# i2c-8ch-mux.net
KiCad netlist of a schematic drawn in EAGLE
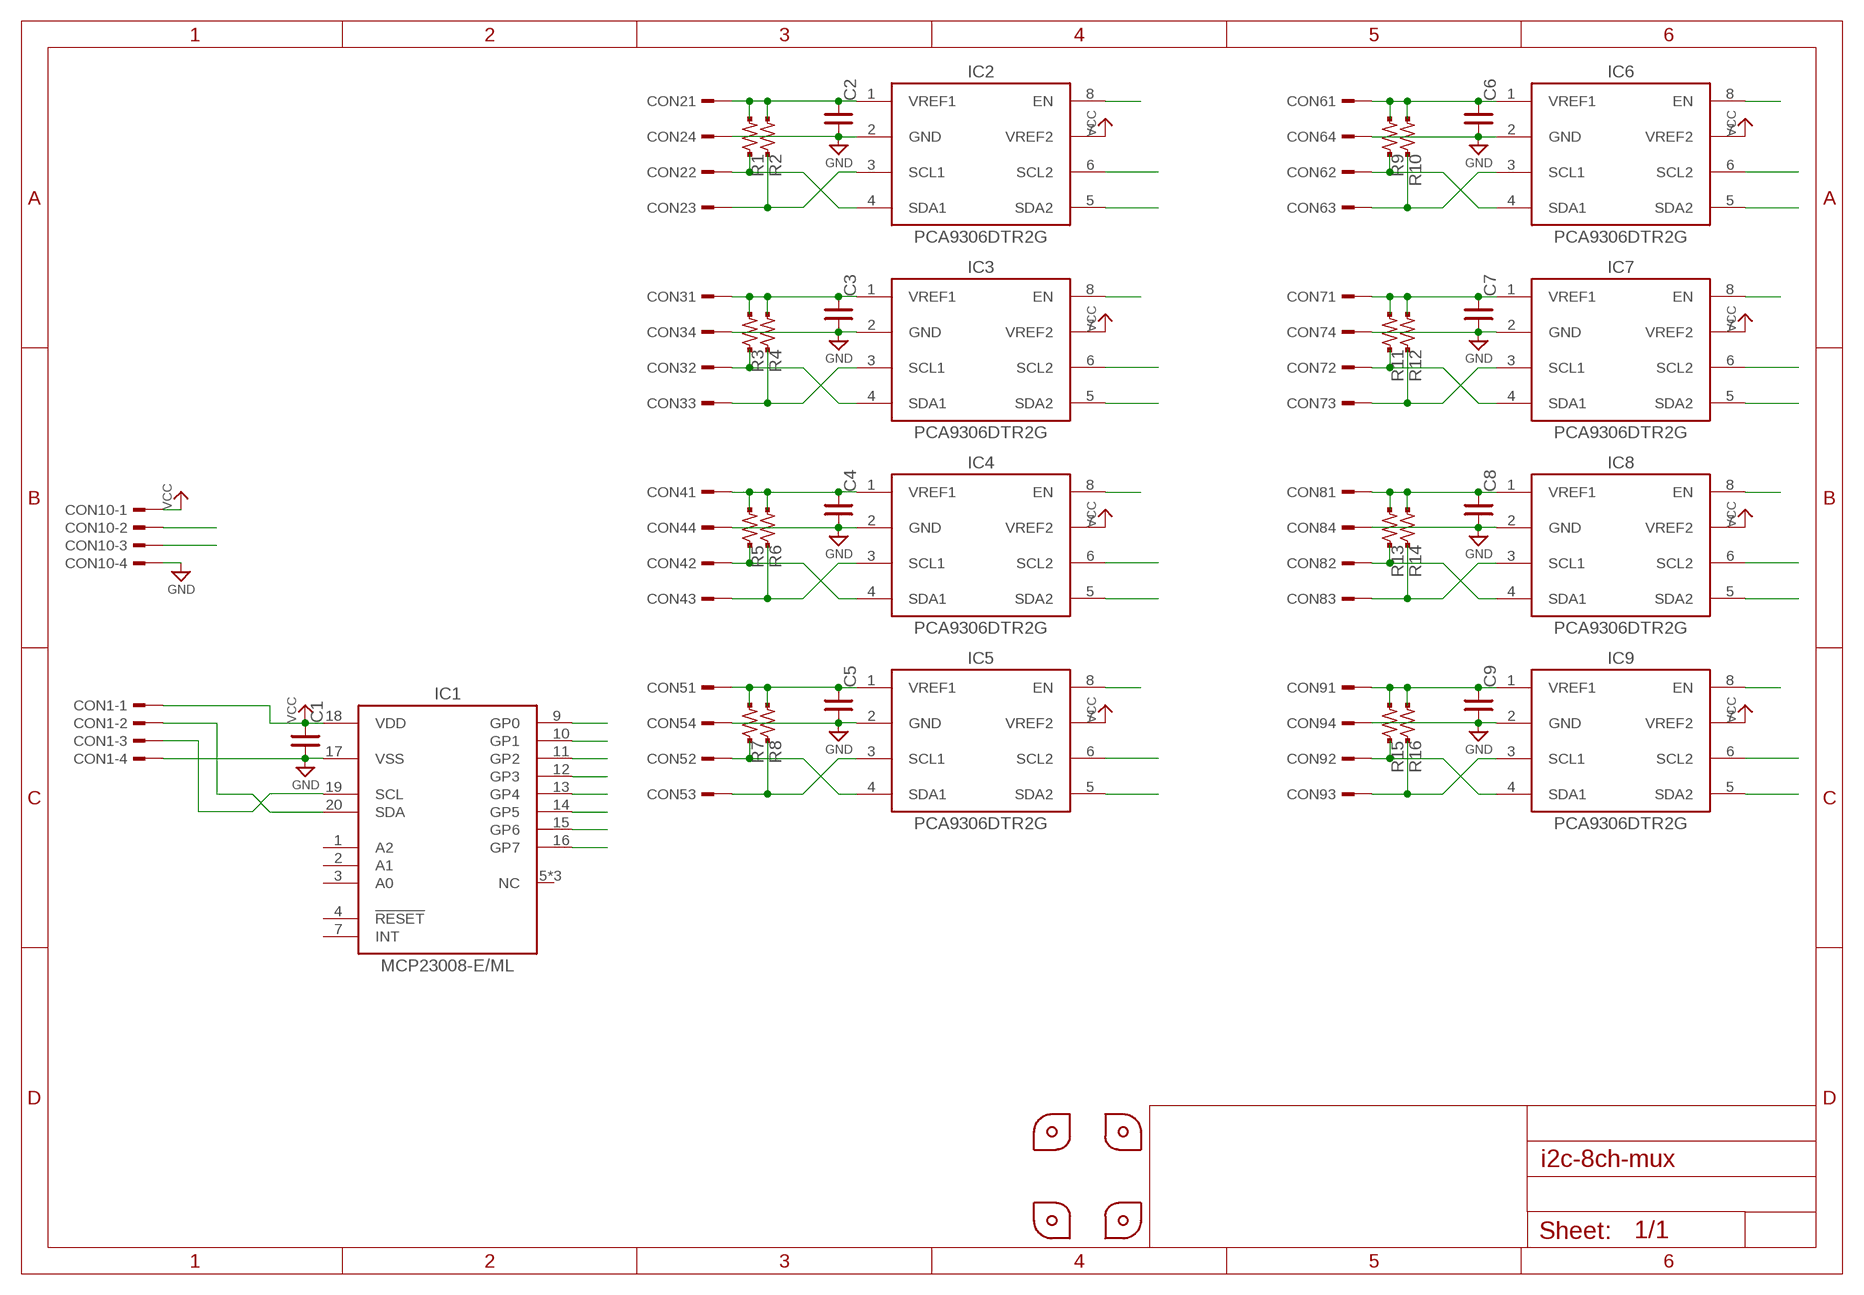
[diagram p0: schematic, sheet 1]

(export (version "E")
  (design (tool "Eeschema 10.0.6"))
  (components
    (comp (ref "C1")
      (value "C-SMD-0.1U-1005")
      (footprint "eagle-import:C0402")
      (libsource (lib "eagle-import") (part "C-SMD--10050.1U"))
    )
    (comp (ref "C2")
      (value "C-SMD-0.1U-1005")
      (footprint "eagle-import:C0402")
      (libsource (lib "eagle-import") (part "C-SMD--10050.1U"))
    )
    (comp (ref "C3")
      (value "C-SMD-0.1U-1005")
      (footprint "eagle-import:C0402")
      (libsource (lib "eagle-import") (part "C-SMD--10050.1U"))
    )
    (comp (ref "C4")
      (value "C-SMD-0.1U-1005")
      (footprint "eagle-import:C0402")
      (libsource (lib "eagle-import") (part "C-SMD--10050.1U"))
    )
    (comp (ref "C5")
      (value "C-SMD-0.1U-1005")
      (footprint "eagle-import:C0402")
      (libsource (lib "eagle-import") (part "C-SMD--10050.1U"))
    )
    (comp (ref "C6")
      (value "C-SMD-0.1U-1005")
      (footprint "eagle-import:C0402")
      (libsource (lib "eagle-import") (part "C-SMD--10050.1U"))
    )
    (comp (ref "C7")
      (value "C-SMD-0.1U-1005")
      (footprint "eagle-import:C0402")
      (libsource (lib "eagle-import") (part "C-SMD--10050.1U"))
    )
    (comp (ref "C8")
      (value "C-SMD-0.1U-1005")
      (footprint "eagle-import:C0402")
      (libsource (lib "eagle-import") (part "C-SMD--10050.1U"))
    )
    (comp (ref "C9")
      (value "C-SMD-0.1U-1005")
      (footprint "eagle-import:C0402")
      (libsource (lib "eagle-import") (part "C-SMD--10050.1U"))
    )
    (comp (ref "CON1")
      (value "S4B-XH-A")
      (footprint "eagle-import:S4B-XH-A(LF)(SN)")
      (libsource (lib "eagle-import") (part "S4B-XH-A"))
    )
    (comp (ref "CON2")
      (value "B4B-XH-A")
      (footprint "eagle-import:B4B-XH-A(LF)(SN)")
      (libsource (lib "eagle-import") (part "B4B-XH-A"))
    )
    (comp (ref "CON3")
      (value "B4B-XH-A")
      (footprint "eagle-import:B4B-XH-A(LF)(SN)")
      (libsource (lib "eagle-import") (part "B4B-XH-A"))
    )
    (comp (ref "CON4")
      (value "B4B-XH-A")
      (footprint "eagle-import:B4B-XH-A(LF)(SN)")
      (libsource (lib "eagle-import") (part "B4B-XH-A"))
    )
    (comp (ref "CON5")
      (value "B4B-XH-A")
      (footprint "eagle-import:B4B-XH-A(LF)(SN)")
      (libsource (lib "eagle-import") (part "B4B-XH-A"))
    )
    (comp (ref "CON6")
      (value "B4B-XH-A")
      (footprint "eagle-import:B4B-XH-A(LF)(SN)")
      (libsource (lib "eagle-import") (part "B4B-XH-A"))
    )
    (comp (ref "CON7")
      (value "B4B-XH-A")
      (footprint "eagle-import:B4B-XH-A(LF)(SN)")
      (libsource (lib "eagle-import") (part "B4B-XH-A"))
    )
    (comp (ref "CON8")
      (value "B4B-XH-A")
      (footprint "eagle-import:B4B-XH-A(LF)(SN)")
      (libsource (lib "eagle-import") (part "B4B-XH-A"))
    )
    (comp (ref "CON9")
      (value "B4B-XH-A")
      (footprint "eagle-import:B4B-XH-A(LF)(SN)")
      (libsource (lib "eagle-import") (part "B4B-XH-A"))
    )
    (comp (ref "CON10")
      (value "S4B-XH-A")
      (footprint "eagle-import:S4B-XH-A(LF)(SN)")
      (libsource (lib "eagle-import") (part "S4B-XH-A"))
    )
    (comp (ref "IC1")
      (value "MCP23008-E/ML")
      (footprint "eagle-import:QFN20-0.5P4.0X4.0")
      (libsource (lib "eagle-import") (part "MCP23008/ML-E"))
    )
    (comp (ref "IC2")
      (value "PCA9306DTR2G")
      (footprint "eagle-import:SOT65P440X300-8N")
      (libsource (lib "eagle-import") (part "PCA9306R2GDT"))
    )
    (comp (ref "IC3")
      (value "PCA9306DTR2G")
      (footprint "eagle-import:SOT65P440X300-8N")
      (libsource (lib "eagle-import") (part "PCA9306R2GDT"))
    )
    (comp (ref "IC4")
      (value "PCA9306DTR2G")
      (footprint "eagle-import:SOT65P440X300-8N")
      (libsource (lib "eagle-import") (part "PCA9306R2GDT"))
    )
    (comp (ref "IC5")
      (value "PCA9306DTR2G")
      (footprint "eagle-import:SOT65P440X300-8N")
      (libsource (lib "eagle-import") (part "PCA9306R2GDT"))
    )
    (comp (ref "IC6")
      (value "PCA9306DTR2G")
      (footprint "eagle-import:SOT65P440X300-8N")
      (libsource (lib "eagle-import") (part "PCA9306R2GDT"))
    )
    (comp (ref "IC7")
      (value "PCA9306DTR2G")
      (footprint "eagle-import:SOT65P440X300-8N")
      (libsource (lib "eagle-import") (part "PCA9306R2GDT"))
    )
    (comp (ref "IC8")
      (value "PCA9306DTR2G")
      (footprint "eagle-import:SOT65P440X300-8N")
      (libsource (lib "eagle-import") (part "PCA9306R2GDT"))
    )
    (comp (ref "IC9")
      (value "PCA9306DTR2G")
      (footprint "eagle-import:SOT65P440X300-8N")
      (libsource (lib "eagle-import") (part "PCA9306R2GDT"))
    )
    (comp (ref "P1")
      (value "PCB-CORNER")
      (footprint "eagle-import:PCB-CORNER")
      (libsource (lib "eagle-import") (part "PCB-CORNER"))
    )
    (comp (ref "P2")
      (value "PCB-CORNER")
      (footprint "eagle-import:PCB-CORNER")
      (libsource (lib "eagle-import") (part "PCB-CORNER"))
    )
    (comp (ref "P3")
      (value "PCB-CORNER")
      (footprint "eagle-import:PCB-CORNER")
      (libsource (lib "eagle-import") (part "PCB-CORNER"))
    )
    (comp (ref "P4")
      (value "PCB-CORNER")
      (footprint "eagle-import:PCB-CORNER")
      (libsource (lib "eagle-import") (part "PCB-CORNER"))
    )
    (comp (ref "R1")
      (value "R-US-10K-1005")
      (footprint "eagle-import:C0402")
      (libsource (lib "eagle-import") (part "R-US--100510K"))
    )
    (comp (ref "R2")
      (value "R-US-10K-1005")
      (footprint "eagle-import:C0402")
      (libsource (lib "eagle-import") (part "R-US--100510K"))
    )
    (comp (ref "R3")
      (value "R-US-10K-1005")
      (footprint "eagle-import:C0402")
      (libsource (lib "eagle-import") (part "R-US--100510K"))
    )
    (comp (ref "R4")
      (value "R-US-10K-1005")
      (footprint "eagle-import:C0402")
      (libsource (lib "eagle-import") (part "R-US--100510K"))
    )
    (comp (ref "R5")
      (value "R-US-10K-1005")
      (footprint "eagle-import:C0402")
      (libsource (lib "eagle-import") (part "R-US--100510K"))
    )
    (comp (ref "R6")
      (value "R-US-10K-1005")
      (footprint "eagle-import:C0402")
      (libsource (lib "eagle-import") (part "R-US--100510K"))
    )
    (comp (ref "R7")
      (value "R-US-10K-1005")
      (footprint "eagle-import:C0402")
      (libsource (lib "eagle-import") (part "R-US--100510K"))
    )
    (comp (ref "R8")
      (value "R-US-10K-1005")
      (footprint "eagle-import:C0402")
      (libsource (lib "eagle-import") (part "R-US--100510K"))
    )
    (comp (ref "R9")
      (value "R-US-10K-1005")
      (footprint "eagle-import:C0402")
      (libsource (lib "eagle-import") (part "R-US--100510K"))
    )
    (comp (ref "R10")
      (value "R-US-10K-1005")
      (footprint "eagle-import:C0402")
      (libsource (lib "eagle-import") (part "R-US--100510K"))
    )
    (comp (ref "R11")
      (value "R-US-10K-1005")
      (footprint "eagle-import:C0402")
      (libsource (lib "eagle-import") (part "R-US--100510K"))
    )
    (comp (ref "R12")
      (value "R-US-10K-1005")
      (footprint "eagle-import:C0402")
      (libsource (lib "eagle-import") (part "R-US--100510K"))
    )
    (comp (ref "R13")
      (value "R-US-10K-1005")
      (footprint "eagle-import:C0402")
      (libsource (lib "eagle-import") (part "R-US--100510K"))
    )
    (comp (ref "R14")
      (value "R-US-10K-1005")
      (footprint "eagle-import:C0402")
      (libsource (lib "eagle-import") (part "R-US--100510K"))
    )
    (comp (ref "R15")
      (value "R-US-10K-1005")
      (footprint "eagle-import:C0402")
      (libsource (lib "eagle-import") (part "R-US--100510K"))
    )
    (comp (ref "R16")
      (value "R-US-10K-1005")
      (footprint "eagle-import:C0402")
      (libsource (lib "eagle-import") (part "R-US--100510K"))
    )
  )
  (nets
    (net (code "1") (name "/N$6") (class "Default")
      (node (ref "IC1") (pin "10") (pinfunction "GP1_10") (pintype "bidirectional"))
      (node (ref "IC3") (pin "8") (pinfunction "EN_8") (pintype "bidirectional"))
    )
    (net (code "2") (name "/N$7") (class "Default")
      (node (ref "IC1") (pin "9") (pinfunction "GP0_9") (pintype "bidirectional"))
      (node (ref "IC2") (pin "8") (pinfunction "EN_8") (pintype "bidirectional"))
    )
    (net (code "3") (name "/N$8") (class "Default")
      (node (ref "IC1") (pin "11") (pinfunction "GP2_11") (pintype "bidirectional"))
      (node (ref "IC4") (pin "8") (pinfunction "EN_8") (pintype "bidirectional"))
    )
    (net (code "4") (name "/N$9") (class "Default")
      (node (ref "CON1") (pin "3") (pinfunction "1_3") (pintype "passive"))
      (node (ref "CON10") (pin "3") (pinfunction "1_3") (pintype "passive"))
      (node (ref "IC1") (pin "19") (pinfunction "SCL_19") (pintype "bidirectional"))
      (node (ref "IC2") (pin "6") (pinfunction "SCL2_6") (pintype "bidirectional"))
      (node (ref "IC3") (pin "6") (pinfunction "SCL2_6") (pintype "bidirectional"))
      (node (ref "IC4") (pin "6") (pinfunction "SCL2_6") (pintype "bidirectional"))
      (node (ref "IC5") (pin "6") (pinfunction "SCL2_6") (pintype "bidirectional"))
      (node (ref "IC6") (pin "6") (pinfunction "SCL2_6") (pintype "bidirectional"))
      (node (ref "IC7") (pin "6") (pinfunction "SCL2_6") (pintype "bidirectional"))
      (node (ref "IC8") (pin "6") (pinfunction "SCL2_6") (pintype "bidirectional"))
      (node (ref "IC9") (pin "6") (pinfunction "SCL2_6") (pintype "bidirectional"))
    )
    (net (code "5") (name "/N$10") (class "Default")
      (node (ref "CON1") (pin "2") (pinfunction "1_2") (pintype "passive"))
      (node (ref "CON10") (pin "2") (pinfunction "1_2") (pintype "passive"))
      (node (ref "IC1") (pin "20") (pinfunction "SDA_20") (pintype "bidirectional"))
      (node (ref "IC2") (pin "5") (pinfunction "SDA2_5") (pintype "bidirectional"))
      (node (ref "IC3") (pin "5") (pinfunction "SDA2_5") (pintype "bidirectional"))
      (node (ref "IC4") (pin "5") (pinfunction "SDA2_5") (pintype "bidirectional"))
      (node (ref "IC5") (pin "5") (pinfunction "SDA2_5") (pintype "bidirectional"))
      (node (ref "IC6") (pin "5") (pinfunction "SDA2_5") (pintype "bidirectional"))
      (node (ref "IC7") (pin "5") (pinfunction "SDA2_5") (pintype "bidirectional"))
      (node (ref "IC8") (pin "5") (pinfunction "SDA2_5") (pintype "bidirectional"))
      (node (ref "IC9") (pin "5") (pinfunction "SDA2_5") (pintype "bidirectional"))
    )
    (net (code "6") (name "/N$23") (class "Default")
      (node (ref "IC1") (pin "12") (pinfunction "GP3_12") (pintype "bidirectional"))
      (node (ref "IC5") (pin "8") (pinfunction "EN_8") (pintype "bidirectional"))
    )
    (net (code "7") (name "/N$24") (class "Default")
      (node (ref "IC1") (pin "13") (pinfunction "GP4_13") (pintype "bidirectional"))
      (node (ref "IC6") (pin "8") (pinfunction "EN_8") (pintype "bidirectional"))
    )
    (net (code "8") (name "/N$25") (class "Default")
      (node (ref "IC1") (pin "14") (pinfunction "GP5_14") (pintype "bidirectional"))
      (node (ref "IC7") (pin "8") (pinfunction "EN_8") (pintype "bidirectional"))
    )
    (net (code "9") (name "/N$26") (class "Default")
      (node (ref "IC1") (pin "15") (pinfunction "GP6_15") (pintype "bidirectional"))
      (node (ref "IC8") (pin "8") (pinfunction "EN_8") (pintype "bidirectional"))
    )
    (net (code "10") (name "/N$27") (class "Default")
      (node (ref "IC1") (pin "16") (pinfunction "GP7_16") (pintype "bidirectional"))
      (node (ref "IC9") (pin "8") (pinfunction "EN_8") (pintype "bidirectional"))
    )
    (net (code "11") (name "GND") (class "Default")
      (node (ref "C1") (pin "2") (pinfunction "2_2") (pintype "passive"))
      (node (ref "C2") (pin "2") (pinfunction "2_2") (pintype "passive"))
      (node (ref "C3") (pin "2") (pinfunction "2_2") (pintype "passive"))
      (node (ref "C4") (pin "2") (pinfunction "2_2") (pintype "passive"))
      (node (ref "C5") (pin "2") (pinfunction "2_2") (pintype "passive"))
      (node (ref "C6") (pin "2") (pinfunction "2_2") (pintype "passive"))
      (node (ref "C7") (pin "2") (pinfunction "2_2") (pintype "passive"))
      (node (ref "C8") (pin "2") (pinfunction "2_2") (pintype "passive"))
      (node (ref "C9") (pin "2") (pinfunction "2_2") (pintype "passive"))
      (node (ref "CON1") (pin "4") (pinfunction "1_4") (pintype "passive"))
      (node (ref "CON10") (pin "4") (pinfunction "1_4") (pintype "passive"))
      (node (ref "CON2") (pin "4") (pinfunction "1_4") (pintype "passive"))
      (node (ref "CON3") (pin "4") (pinfunction "1_4") (pintype "passive"))
      (node (ref "CON4") (pin "4") (pinfunction "1_4") (pintype "passive"))
      (node (ref "CON5") (pin "4") (pinfunction "1_4") (pintype "passive"))
      (node (ref "CON6") (pin "4") (pinfunction "1_4") (pintype "passive"))
      (node (ref "CON7") (pin "4") (pinfunction "1_4") (pintype "passive"))
      (node (ref "CON8") (pin "4") (pinfunction "1_4") (pintype "passive"))
      (node (ref "CON9") (pin "4") (pinfunction "1_4") (pintype "passive"))
      (node (ref "IC1") (pin "17") (pinfunction "VSS_17") (pintype "power_in"))
      (node (ref "IC2") (pin "2") (pinfunction "GND_2") (pintype "bidirectional"))
      (node (ref "IC3") (pin "2") (pinfunction "GND_2") (pintype "bidirectional"))
      (node (ref "IC4") (pin "2") (pinfunction "GND_2") (pintype "bidirectional"))
      (node (ref "IC5") (pin "2") (pinfunction "GND_2") (pintype "bidirectional"))
      (node (ref "IC6") (pin "2") (pinfunction "GND_2") (pintype "bidirectional"))
      (node (ref "IC7") (pin "2") (pinfunction "GND_2") (pintype "bidirectional"))
      (node (ref "IC8") (pin "2") (pinfunction "GND_2") (pintype "bidirectional"))
      (node (ref "IC9") (pin "2") (pinfunction "GND_2") (pintype "bidirectional"))
    )
    (net (code "12") (name "Net-(CON2B-1)") (class "Default")
      (node (ref "CON2") (pin "2") (pinfunction "1_2") (pintype "passive"))
      (node (ref "IC2") (pin "4") (pinfunction "SDA1_4") (pintype "bidirectional"))
      (node (ref "R1") (pin "1") (pinfunction "1_1") (pintype "passive"))
    )
    (net (code "13") (name "Net-(CON2C-1)") (class "Default")
      (node (ref "CON2") (pin "3") (pinfunction "1_3") (pintype "passive"))
      (node (ref "IC2") (pin "3") (pinfunction "SCL1_3") (pintype "bidirectional"))
      (node (ref "R2") (pin "1") (pinfunction "1_1") (pintype "passive"))
    )
    (net (code "14") (name "Net-(CON3B-1)") (class "Default")
      (node (ref "CON3") (pin "2") (pinfunction "1_2") (pintype "passive"))
      (node (ref "IC3") (pin "4") (pinfunction "SDA1_4") (pintype "bidirectional"))
      (node (ref "R3") (pin "1") (pinfunction "1_1") (pintype "passive"))
    )
    (net (code "15") (name "Net-(CON3C-1)") (class "Default")
      (node (ref "CON3") (pin "3") (pinfunction "1_3") (pintype "passive"))
      (node (ref "IC3") (pin "3") (pinfunction "SCL1_3") (pintype "bidirectional"))
      (node (ref "R4") (pin "1") (pinfunction "1_1") (pintype "passive"))
    )
    (net (code "16") (name "Net-(CON4B-1)") (class "Default")
      (node (ref "CON4") (pin "2") (pinfunction "1_2") (pintype "passive"))
      (node (ref "IC4") (pin "4") (pinfunction "SDA1_4") (pintype "bidirectional"))
      (node (ref "R5") (pin "1") (pinfunction "1_1") (pintype "passive"))
    )
    (net (code "17") (name "Net-(CON4C-1)") (class "Default")
      (node (ref "CON4") (pin "3") (pinfunction "1_3") (pintype "passive"))
      (node (ref "IC4") (pin "3") (pinfunction "SCL1_3") (pintype "bidirectional"))
      (node (ref "R6") (pin "1") (pinfunction "1_1") (pintype "passive"))
    )
    (net (code "18") (name "Net-(CON5B-1)") (class "Default")
      (node (ref "CON5") (pin "2") (pinfunction "1_2") (pintype "passive"))
      (node (ref "IC5") (pin "4") (pinfunction "SDA1_4") (pintype "bidirectional"))
      (node (ref "R7") (pin "1") (pinfunction "1_1") (pintype "passive"))
    )
    (net (code "19") (name "Net-(CON5C-1)") (class "Default")
      (node (ref "CON5") (pin "3") (pinfunction "1_3") (pintype "passive"))
      (node (ref "IC5") (pin "3") (pinfunction "SCL1_3") (pintype "bidirectional"))
      (node (ref "R8") (pin "1") (pinfunction "1_1") (pintype "passive"))
    )
    (net (code "20") (name "Net-(CON6B-1)") (class "Default")
      (node (ref "CON6") (pin "2") (pinfunction "1_2") (pintype "passive"))
      (node (ref "IC6") (pin "4") (pinfunction "SDA1_4") (pintype "bidirectional"))
      (node (ref "R9") (pin "1") (pinfunction "1_1") (pintype "passive"))
    )
    (net (code "21") (name "Net-(CON6C-1)") (class "Default")
      (node (ref "CON6") (pin "3") (pinfunction "1_3") (pintype "passive"))
      (node (ref "IC6") (pin "3") (pinfunction "SCL1_3") (pintype "bidirectional"))
      (node (ref "R10") (pin "1") (pinfunction "1_1") (pintype "passive"))
    )
    (net (code "22") (name "Net-(CON7B-1)") (class "Default")
      (node (ref "CON7") (pin "2") (pinfunction "1_2") (pintype "passive"))
      (node (ref "IC7") (pin "4") (pinfunction "SDA1_4") (pintype "bidirectional"))
      (node (ref "R11") (pin "1") (pinfunction "1_1") (pintype "passive"))
    )
    (net (code "23") (name "Net-(CON7C-1)") (class "Default")
      (node (ref "CON7") (pin "3") (pinfunction "1_3") (pintype "passive"))
      (node (ref "IC7") (pin "3") (pinfunction "SCL1_3") (pintype "bidirectional"))
      (node (ref "R12") (pin "1") (pinfunction "1_1") (pintype "passive"))
    )
    (net (code "24") (name "Net-(CON8B-1)") (class "Default")
      (node (ref "CON8") (pin "2") (pinfunction "1_2") (pintype "passive"))
      (node (ref "IC8") (pin "4") (pinfunction "SDA1_4") (pintype "bidirectional"))
      (node (ref "R13") (pin "1") (pinfunction "1_1") (pintype "passive"))
    )
    (net (code "25") (name "Net-(CON8C-1)") (class "Default")
      (node (ref "CON8") (pin "3") (pinfunction "1_3") (pintype "passive"))
      (node (ref "IC8") (pin "3") (pinfunction "SCL1_3") (pintype "bidirectional"))
      (node (ref "R14") (pin "1") (pinfunction "1_1") (pintype "passive"))
    )
    (net (code "26") (name "Net-(CON9B-1)") (class "Default")
      (node (ref "CON9") (pin "2") (pinfunction "1_2") (pintype "passive"))
      (node (ref "IC9") (pin "4") (pinfunction "SDA1_4") (pintype "bidirectional"))
      (node (ref "R15") (pin "1") (pinfunction "1_1") (pintype "passive"))
    )
    (net (code "27") (name "Net-(CON9C-1)") (class "Default")
      (node (ref "CON9") (pin "3") (pinfunction "1_3") (pintype "passive"))
      (node (ref "IC9") (pin "3") (pinfunction "SCL1_3") (pintype "bidirectional"))
      (node (ref "R16") (pin "1") (pinfunction "1_1") (pintype "passive"))
    )
    (net (code "28") (name "Net-(IC2-VREF1)") (class "Default")
      (node (ref "C2") (pin "1") (pinfunction "1_1") (pintype "passive"))
      (node (ref "CON2") (pin "1") (pinfunction "1_1") (pintype "passive"))
      (node (ref "IC2") (pin "1") (pinfunction "VREF1_1") (pintype "bidirectional"))
      (node (ref "R1") (pin "2") (pinfunction "2_2") (pintype "passive"))
      (node (ref "R2") (pin "2") (pinfunction "2_2") (pintype "passive"))
    )
    (net (code "29") (name "Net-(IC3-VREF1)") (class "Default")
      (node (ref "C3") (pin "1") (pinfunction "1_1") (pintype "passive"))
      (node (ref "CON3") (pin "1") (pinfunction "1_1") (pintype "passive"))
      (node (ref "IC3") (pin "1") (pinfunction "VREF1_1") (pintype "bidirectional"))
      (node (ref "R3") (pin "2") (pinfunction "2_2") (pintype "passive"))
      (node (ref "R4") (pin "2") (pinfunction "2_2") (pintype "passive"))
    )
    (net (code "30") (name "Net-(IC4-VREF1)") (class "Default")
      (node (ref "C4") (pin "1") (pinfunction "1_1") (pintype "passive"))
      (node (ref "CON4") (pin "1") (pinfunction "1_1") (pintype "passive"))
      (node (ref "IC4") (pin "1") (pinfunction "VREF1_1") (pintype "bidirectional"))
      (node (ref "R5") (pin "2") (pinfunction "2_2") (pintype "passive"))
      (node (ref "R6") (pin "2") (pinfunction "2_2") (pintype "passive"))
    )
    (net (code "31") (name "Net-(IC5-VREF1)") (class "Default")
      (node (ref "C5") (pin "1") (pinfunction "1_1") (pintype "passive"))
      (node (ref "CON5") (pin "1") (pinfunction "1_1") (pintype "passive"))
      (node (ref "IC5") (pin "1") (pinfunction "VREF1_1") (pintype "bidirectional"))
      (node (ref "R7") (pin "2") (pinfunction "2_2") (pintype "passive"))
      (node (ref "R8") (pin "2") (pinfunction "2_2") (pintype "passive"))
    )
    (net (code "32") (name "Net-(IC6-VREF1)") (class "Default")
      (node (ref "C6") (pin "1") (pinfunction "1_1") (pintype "passive"))
      (node (ref "CON6") (pin "1") (pinfunction "1_1") (pintype "passive"))
      (node (ref "IC6") (pin "1") (pinfunction "VREF1_1") (pintype "bidirectional"))
      (node (ref "R10") (pin "2") (pinfunction "2_2") (pintype "passive"))
      (node (ref "R9") (pin "2") (pinfunction "2_2") (pintype "passive"))
    )
    (net (code "33") (name "Net-(IC7-VREF1)") (class "Default")
      (node (ref "C7") (pin "1") (pinfunction "1_1") (pintype "passive"))
      (node (ref "CON7") (pin "1") (pinfunction "1_1") (pintype "passive"))
      (node (ref "IC7") (pin "1") (pinfunction "VREF1_1") (pintype "bidirectional"))
      (node (ref "R11") (pin "2") (pinfunction "2_2") (pintype "passive"))
      (node (ref "R12") (pin "2") (pinfunction "2_2") (pintype "passive"))
    )
    (net (code "34") (name "Net-(IC8-VREF1)") (class "Default")
      (node (ref "C8") (pin "1") (pinfunction "1_1") (pintype "passive"))
      (node (ref "CON8") (pin "1") (pinfunction "1_1") (pintype "passive"))
      (node (ref "IC8") (pin "1") (pinfunction "VREF1_1") (pintype "bidirectional"))
      (node (ref "R13") (pin "2") (pinfunction "2_2") (pintype "passive"))
      (node (ref "R14") (pin "2") (pinfunction "2_2") (pintype "passive"))
    )
    (net (code "35") (name "Net-(IC9-VREF1)") (class "Default")
      (node (ref "C9") (pin "1") (pinfunction "1_1") (pintype "passive"))
      (node (ref "CON9") (pin "1") (pinfunction "1_1") (pintype "passive"))
      (node (ref "IC9") (pin "1") (pinfunction "VREF1_1") (pintype "bidirectional"))
      (node (ref "R15") (pin "2") (pinfunction "2_2") (pintype "passive"))
      (node (ref "R16") (pin "2") (pinfunction "2_2") (pintype "passive"))
    )
    (net (code "36") (name "VCC") (class "Default")
      (node (ref "C1") (pin "1") (pinfunction "1_1") (pintype "passive"))
      (node (ref "CON1") (pin "1") (pinfunction "1_1") (pintype "passive"))
      (node (ref "CON10") (pin "1") (pinfunction "1_1") (pintype "passive"))
      (node (ref "IC1") (pin "18") (pinfunction "VDD_18") (pintype "power_in"))
      (node (ref "IC2") (pin "7") (pinfunction "VREF2_7") (pintype "bidirectional"))
      (node (ref "IC3") (pin "7") (pinfunction "VREF2_7") (pintype "bidirectional"))
      (node (ref "IC4") (pin "7") (pinfunction "VREF2_7") (pintype "bidirectional"))
      (node (ref "IC5") (pin "7") (pinfunction "VREF2_7") (pintype "bidirectional"))
      (node (ref "IC6") (pin "7") (pinfunction "VREF2_7") (pintype "bidirectional"))
      (node (ref "IC7") (pin "7") (pinfunction "VREF2_7") (pintype "bidirectional"))
      (node (ref "IC8") (pin "7") (pinfunction "VREF2_7") (pintype "bidirectional"))
      (node (ref "IC9") (pin "7") (pinfunction "VREF2_7") (pintype "bidirectional"))
    )
    (net (code "37") (name "unconnected-(IC1-A0-Pad3)") (class "Default")
      (node (ref "IC1") (pin "3") (pinfunction "A0_3") (pintype "bidirectional"))
    )
    (net (code "38") (name "unconnected-(IC1-A1-Pad2)") (class "Default")
      (node (ref "IC1") (pin "2") (pinfunction "A1_2") (pintype "bidirectional"))
    )
    (net (code "39") (name "unconnected-(IC1-A2-Pad1)") (class "Default")
      (node (ref "IC1") (pin "1") (pinfunction "A2_1") (pintype "bidirectional"))
    )
    (net (code "40") (name "unconnected-(IC1-INT-Pad7)") (class "Default")
      (node (ref "IC1") (pin "7") (pinfunction "INT_7") (pintype "bidirectional"))
    )
    (net (code "41") (name "unconnected-(IC1-NC-Pad5)") (class "Default")
      (node (ref "IC1") (pin "5") (pinfunction "NC_5") (pintype "no_connect"))
    )
    (net (code "42") (name "unconnected-(IC1-NC-Pad6)") (class "Default")
      (node (ref "IC1") (pin "6") (pinfunction "NC_6") (pintype "no_connect"))
    )
    (net (code "43") (name "unconnected-(IC1-NC-Pad8)") (class "Default")
      (node (ref "IC1") (pin "8") (pinfunction "NC_8") (pintype "no_connect"))
    )
    (net (code "44") (name "unconnected-(IC1-~{RESET}-Pad4)") (class "Default")
      (node (ref "IC1") (pin "4") (pinfunction "~{RESET}_4") (pintype "bidirectional"))
    )
  )
)
